# SCH_hack-club-pcb_2025-02-10.net
KiCad netlist of a schematic drawn in EasyEDA
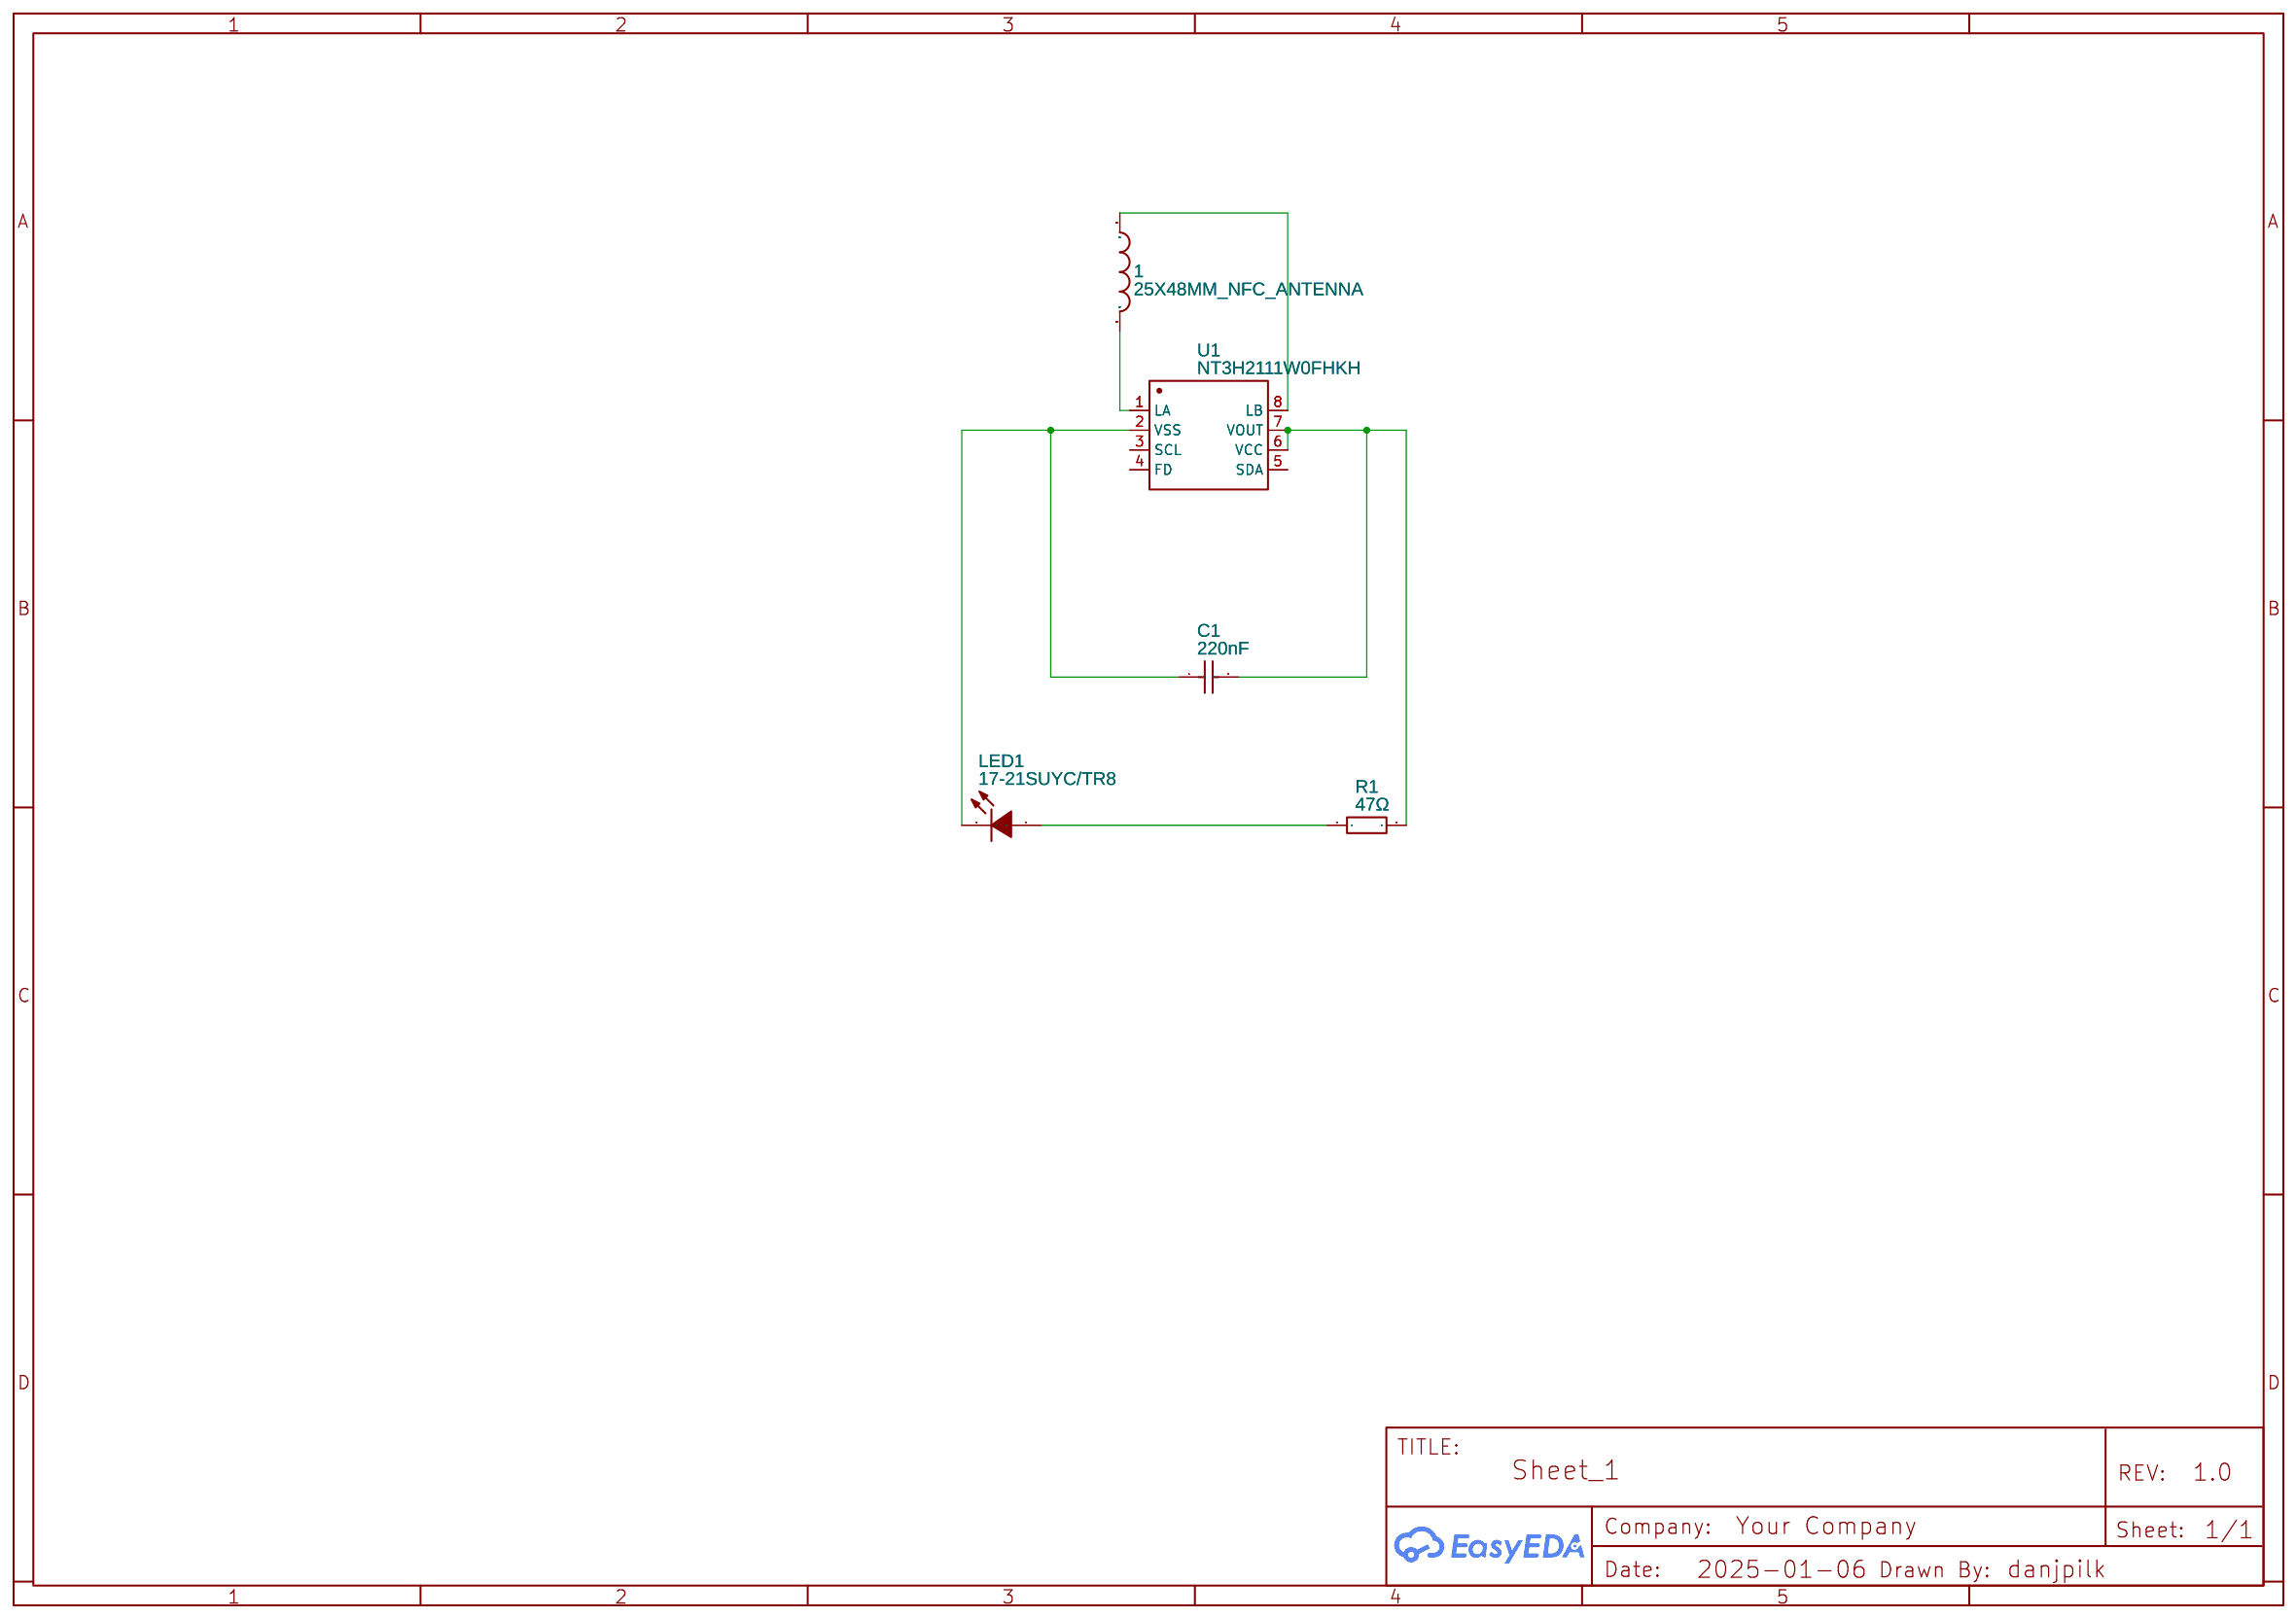
[diagram p0: schematic sheet]

(export (version "E")
  (design (tool "Eeschema 10.0.6"))
  (components
    (comp (ref "1") (value "25X48MM_NFC_ANTENNA") (libsource (lib "") (part "25X48MM_NFC_ANTENNA")))
    (comp (ref "C1")
      (value "220nF")
      (fields
        (field (name "Manufacturer Part") "CL10B224KA8NNNC")
        (field (name "Manufacturer") "SAMSUNG(三星)")
      )
      (libsource (lib "") (part "CL10B224KA8NNNC"))
    )
    (comp (ref "LED1")
      (value "17-21SUYC/TR8")
      (fields (field (name "Manufacturer Part") "KT-0805黄灯") (field (name "Manufacturer") "KENTO"))
      (libsource (lib "") (part "17-21SUYC/TR8"))
    )
    (comp (ref "R1")
      (value "47Ω")
      (fields
        (field (name "Manufacturer Part") "0603WAF470JT5E")
        (field (name "Manufacturer") "UNI-ROYAL(厚声)")
      )
      (libsource (lib "") (part "0603WAF470JT5E"))
    )
    (comp (ref "U1")
      (value "NT3H2111W0FHKH")
      (fields (field (name "Manufacturer") "NXP(恩智浦)"))
      (libsource (lib "") (part "NT3H2111W0FHKH"))
    )
  )
  (nets
    (net (code "1") (name "Net-(LED1-+)") (class "Default")
      (node (ref "LED1") (pin "1") (pinfunction "+_1") (pintype "unspecified"))
      (node (ref "R1") (pin "1") (pinfunction "1_1") (pintype "input"))
    )
    (net (code "2") (name "Net-(LED1--)") (class "Default")
      (node (ref "C1") (pin "1") (pinfunction "1_1") (pintype "input"))
      (node (ref "LED1") (pin "2") (pinfunction "-_2") (pintype "unspecified"))
      (node (ref "U1") (pin "2") (pinfunction "VSS_2") (pintype "unspecified"))
    )
    (net (code "3") (name "Net-(U1-LA)") (class "Default")
      (node (ref "1") (pin "P$2") (pinfunction "P$2_P$2") (pintype "bidirectional"))
      (node (ref "U1") (pin "1") (pinfunction "LA_1") (pintype "unspecified"))
    )
    (net (code "4") (name "Net-(U1-LB)") (class "Default")
      (node (ref "1") (pin "P$1") (pinfunction "P$1_P$1") (pintype "bidirectional"))
      (node (ref "U1") (pin "8") (pinfunction "LB_8") (pintype "unspecified"))
    )
    (net (code "5") (name "Net-(U1-VCC)") (class "Default")
      (node (ref "C1") (pin "2") (pinfunction "2_2") (pintype "input"))
      (node (ref "R1") (pin "2") (pinfunction "2_2") (pintype "input"))
      (node (ref "U1") (pin "6") (pinfunction "VCC_6") (pintype "unspecified"))
      (node (ref "U1") (pin "7") (pinfunction "VOUT_7") (pintype "unspecified"))
    )
    (net (code "6") (name "unconnected-(U1-FD-Pad4)") (class "Default")
      (node (ref "U1") (pin "4") (pinfunction "FD_4") (pintype "unspecified"))
    )
    (net (code "7") (name "unconnected-(U1-SCL-Pad3)") (class "Default")
      (node (ref "U1") (pin "3") (pinfunction "SCL_3") (pintype "unspecified"))
    )
    (net (code "8") (name "unconnected-(U1-SDA-Pad5)") (class "Default")
      (node (ref "U1") (pin "5") (pinfunction "SDA_5") (pintype "unspecified"))
    )
  )
)
